# teensy_sid.net
KiCad netlist of a schematic drawn in EAGLE
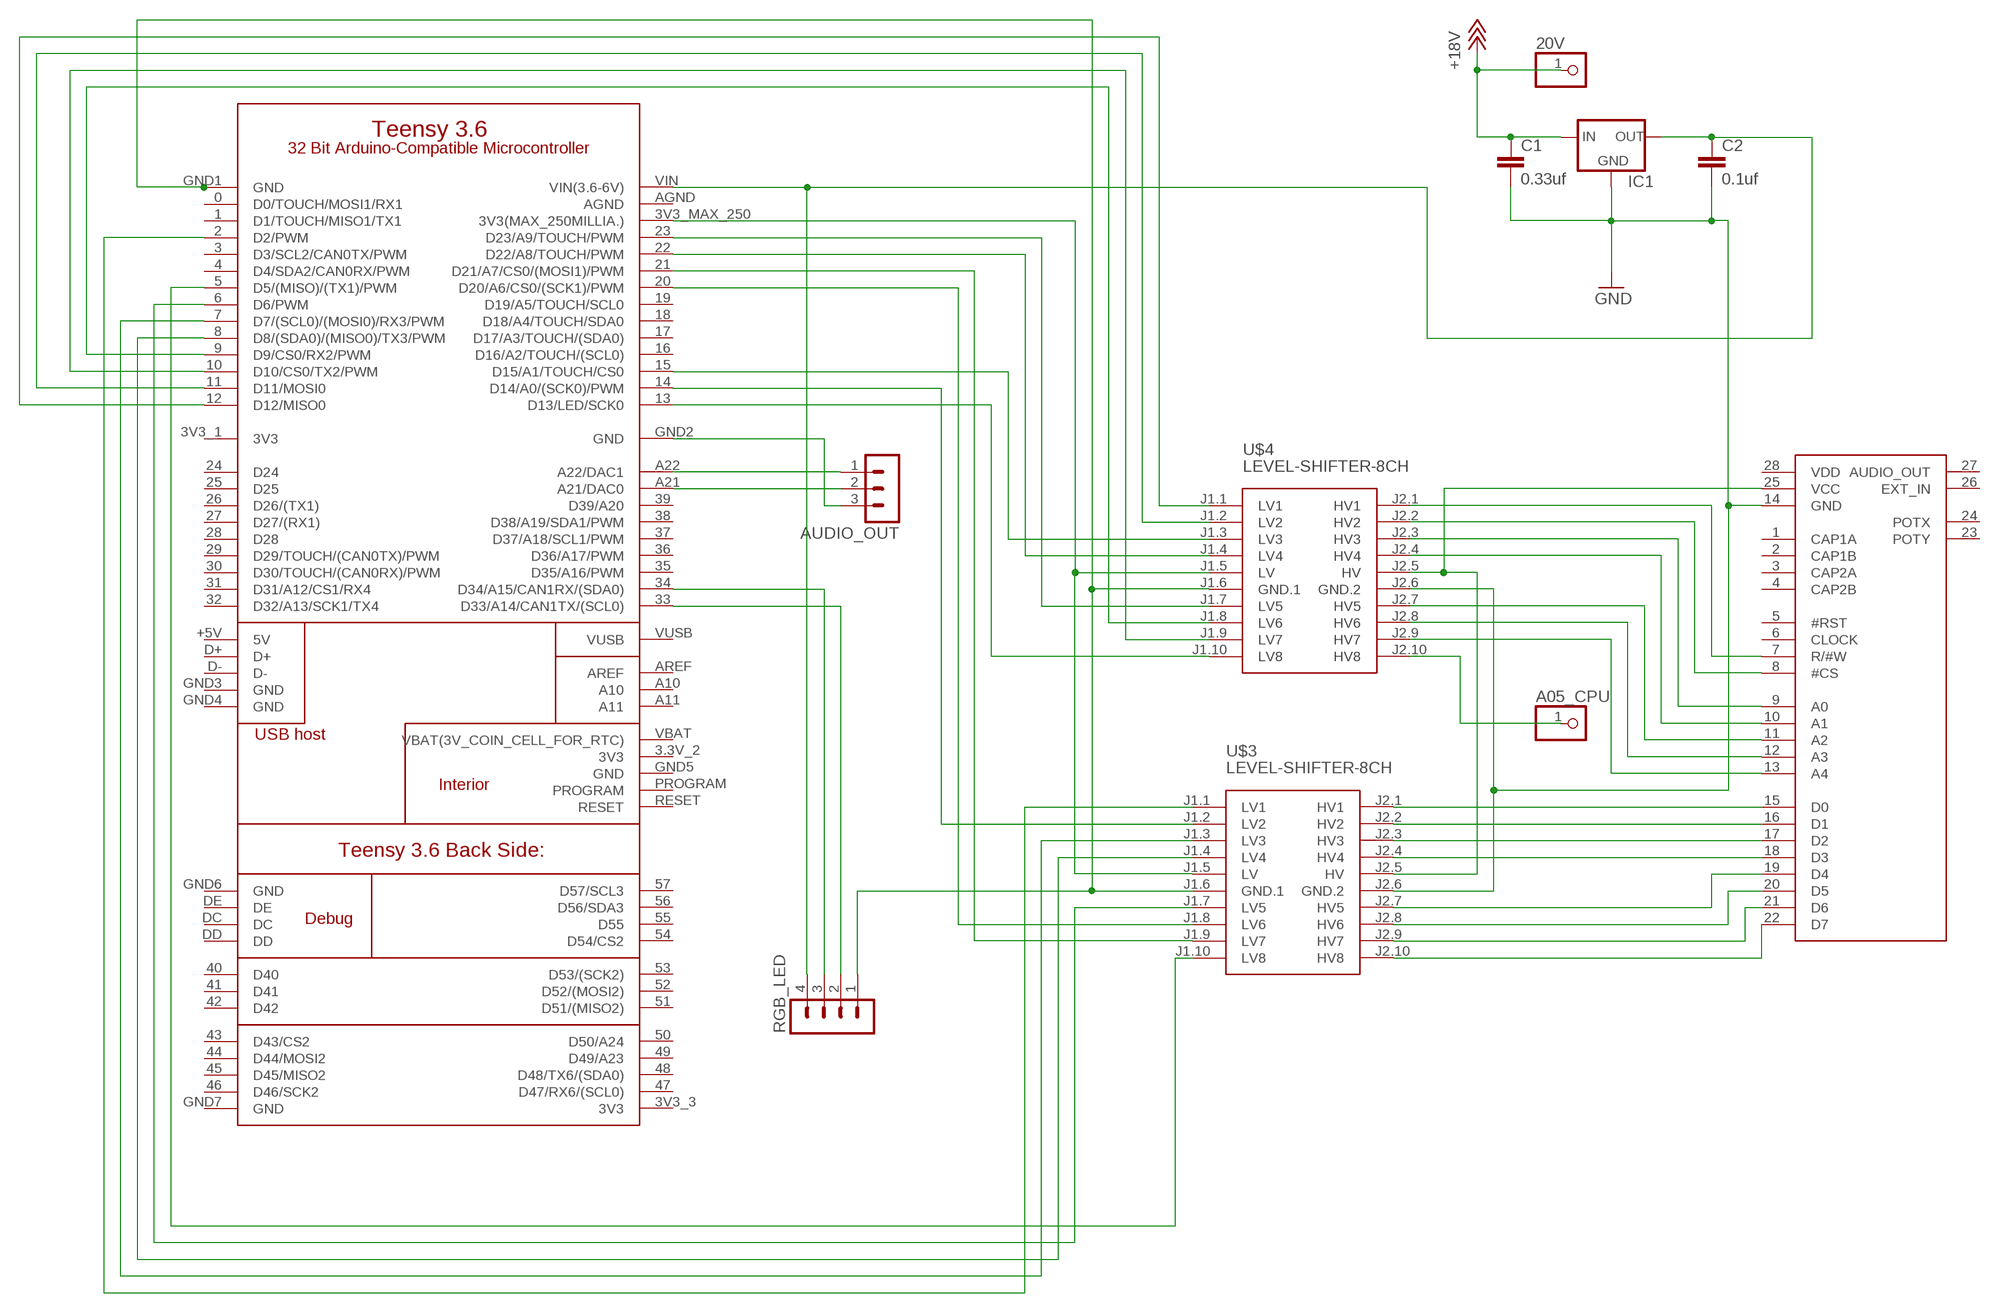
[diagram p0: schematic, sheet 1]

(export (version "E")
  (design (tool "Eeschema 10.0.6"))
  (components
    (comp (ref "20V")
      (value "PINHD-1X1")
      (footprint "eagle-import:1X01")
      (libsource (lib "eagle-import") (part "PINHD-1X1"))
    )
    (comp (ref "A05_CPU")
      (value "PINHD-1X1")
      (footprint "eagle-import:1X01")
      (libsource (lib "eagle-import") (part "PINHD-1X1"))
    )
    (comp (ref "AUDIO_OUT")
      (value "MA03-1")
      (footprint "eagle-import:MA03-1")
      (libsource (lib "eagle-import") (part "MA03-1"))
    )
    (comp (ref "C1")
      (value "0.33uf")
      (footprint "eagle-import:C025-024X044")
      (libsource (lib "eagle-import") (part "C-EU025-024X044"))
    )
    (comp (ref "C2")
      (value "0.1uf")
      (footprint "eagle-import:C025-024X044")
      (libsource (lib "eagle-import") (part "C-EU025-024X044"))
    )
    (comp (ref "IC1")
      (value "78XXL")
      (footprint "eagle-import:78XXL")
      (libsource (lib "eagle-import") (part "78XXL"))
    )
    (comp (ref "RGB_LED")
      (value "MA04-1")
      (footprint "eagle-import:MA04-1")
      (libsource (lib "eagle-import") (part "MA04-1"))
    )
    (comp (ref "U$1")
      (value "SID_6581")
      (footprint "eagle-import:DIL28-6")
      (libsource (lib "eagle-import") (part "SID_6581"))
    )
    (comp (ref "U$2")
      (value "TEENSY-3.6_FULL")
      (footprint "eagle-import:TEENSY-3.6_FULL")
      (libsource (lib "eagle-import") (part "TEENSY-3.6_FULL"))
    )
    (comp (ref "U$3")
      (value "LEVEL-SHIFTER-8CH")
      (footprint "eagle-import:LEVEL-SHIFTER-8CH")
      (libsource (lib "eagle-import") (part "LEVEL-SHIFTER-8CH"))
    )
    (comp (ref "U$4")
      (value "LEVEL-SHIFTER-8CH")
      (footprint "eagle-import:LEVEL-SHIFTER-8CH")
      (libsource (lib "eagle-import") (part "LEVEL-SHIFTER-8CH"))
    )
  )
  (nets
    (net (code "1") (name "+18V") (class "Default")
      (node (ref "20V") (pin "1") (pinfunction "1_1") (pintype "passive"))
      (node (ref "C1") (pin "1") (pinfunction "1_1") (pintype "passive"))
      (node (ref "IC1") (pin "IN") (pinfunction "IN_IN") (pintype "input"))
    )
    (net (code "2") (name "/3V3") (class "Default")
      (node (ref "U$2") (pin "3V3_1") (pinfunction "3V3_3V3_1") (pintype "power_in"))
    )
    (net (code "3") (name "/AGND") (class "Default")
      (node (ref "U$2") (pin "AGND") (pinfunction "AGND_AGND") (pintype "power_in"))
    )
    (net (code "4") (name "GND") (class "Default")
      (node (ref "C1") (pin "2") (pinfunction "2_2") (pintype "passive"))
      (node (ref "C2") (pin "2") (pinfunction "2_2") (pintype "passive"))
      (node (ref "IC1") (pin "GND") (pinfunction "GND_GND") (pintype "input"))
      (node (ref "U$1") (pin "14") (pinfunction "GND_14") (pintype "bidirectional"))
      (node (ref "U$3") (pin "J2.6") (pinfunction "GND.2_J2.6") (pintype "power_in"))
      (node (ref "U$4") (pin "J2.6") (pinfunction "GND.2_J2.6") (pintype "power_in"))
    )
    (net (code "5") (name "Net-(AUDIO_OUT-Pad3)") (class "Default")
      (node (ref "AUDIO_OUT") (pin "3") (pinfunction "3_3") (pintype "passive"))
      (node (ref "U$2") (pin "GND2") (pinfunction "GND_GND2") (pintype "power_in"))
    )
    (net (code "6") (name "Net-(U$1-#CS)") (class "Default")
      (node (ref "U$1") (pin "8") (pinfunction "#CS_8") (pintype "bidirectional"))
      (node (ref "U$4") (pin "J2.2") (pinfunction "HV2_J2.2") (pintype "bidirectional"))
    )
    (net (code "7") (name "Net-(U$1-A0)") (class "Default")
      (node (ref "U$1") (pin "9") (pinfunction "A0_9") (pintype "bidirectional"))
      (node (ref "U$4") (pin "J2.3") (pinfunction "HV3_J2.3") (pintype "bidirectional"))
    )
    (net (code "8") (name "Net-(U$1-A1)") (class "Default")
      (node (ref "U$1") (pin "10") (pinfunction "A1_10") (pintype "bidirectional"))
      (node (ref "U$4") (pin "J2.4") (pinfunction "HV4_J2.4") (pintype "bidirectional"))
    )
    (net (code "9") (name "Net-(U$1-A2)") (class "Default")
      (node (ref "U$1") (pin "11") (pinfunction "A2_11") (pintype "bidirectional"))
      (node (ref "U$4") (pin "J2.7") (pinfunction "HV5_J2.7") (pintype "bidirectional"))
    )
    (net (code "10") (name "Net-(U$1-A3)") (class "Default")
      (node (ref "U$1") (pin "12") (pinfunction "A3_12") (pintype "bidirectional"))
      (node (ref "U$4") (pin "J2.8") (pinfunction "HV6_J2.8") (pintype "bidirectional"))
    )
    (net (code "11") (name "Net-(U$1-A4)") (class "Default")
      (node (ref "U$1") (pin "13") (pinfunction "A4_13") (pintype "bidirectional"))
      (node (ref "U$4") (pin "J2.9") (pinfunction "HV7_J2.9") (pintype "bidirectional"))
    )
    (net (code "12") (name "Net-(U$1-D0)") (class "Default")
      (node (ref "U$1") (pin "15") (pinfunction "D0_15") (pintype "bidirectional"))
      (node (ref "U$3") (pin "J2.1") (pinfunction "HV1_J2.1") (pintype "bidirectional"))
    )
    (net (code "13") (name "Net-(U$1-D1)") (class "Default")
      (node (ref "U$1") (pin "16") (pinfunction "D1_16") (pintype "bidirectional"))
      (node (ref "U$3") (pin "J2.2") (pinfunction "HV2_J2.2") (pintype "bidirectional"))
    )
    (net (code "14") (name "Net-(U$1-D2)") (class "Default")
      (node (ref "U$1") (pin "17") (pinfunction "D2_17") (pintype "bidirectional"))
      (node (ref "U$3") (pin "J2.3") (pinfunction "HV3_J2.3") (pintype "bidirectional"))
    )
    (net (code "15") (name "Net-(U$1-D3)") (class "Default")
      (node (ref "U$1") (pin "18") (pinfunction "D3_18") (pintype "bidirectional"))
      (node (ref "U$3") (pin "J2.4") (pinfunction "HV4_J2.4") (pintype "bidirectional"))
    )
    (net (code "16") (name "Net-(U$1-D4)") (class "Default")
      (node (ref "U$1") (pin "19") (pinfunction "D4_19") (pintype "bidirectional"))
      (node (ref "U$3") (pin "J2.7") (pinfunction "HV5_J2.7") (pintype "bidirectional"))
    )
    (net (code "17") (name "Net-(U$1-D5)") (class "Default")
      (node (ref "U$1") (pin "20") (pinfunction "D5_20") (pintype "bidirectional"))
      (node (ref "U$3") (pin "J2.8") (pinfunction "HV6_J2.8") (pintype "bidirectional"))
    )
    (net (code "18") (name "Net-(U$1-D6)") (class "Default")
      (node (ref "U$1") (pin "21") (pinfunction "D6_21") (pintype "bidirectional"))
      (node (ref "U$3") (pin "J2.9") (pinfunction "HV7_J2.9") (pintype "bidirectional"))
    )
    (net (code "19") (name "Net-(U$1-D7)") (class "Default")
      (node (ref "U$1") (pin "22") (pinfunction "D7_22") (pintype "bidirectional"))
      (node (ref "U$3") (pin "J2.10") (pinfunction "HV8_J2.10") (pintype "bidirectional"))
    )
    (net (code "20") (name "Net-(U$1-R{slash}#W)") (class "Default")
      (node (ref "U$1") (pin "7") (pinfunction "R/#W_7") (pintype "bidirectional"))
      (node (ref "U$4") (pin "J2.1") (pinfunction "HV1_J2.1") (pintype "bidirectional"))
    )
    (net (code "21") (name "Net-(U$1-VCC)") (class "Default")
      (node (ref "U$1") (pin "25") (pinfunction "VCC_25") (pintype "bidirectional"))
      (node (ref "U$3") (pin "J2.5") (pinfunction "HV_J2.5") (pintype "power_in"))
      (node (ref "U$4") (pin "J2.5") (pinfunction "HV_J2.5") (pintype "power_in"))
    )
    (net (code "22") (name "Net-(U$2-3V3(MAX_250MILLIA.))") (class "Default")
      (node (ref "U$2") (pin "3V3_MAX_250") (pinfunction "3V3(MAX_250MILLIA.)_3V3_MAX_250") (pintype "bidirectional"))
      (node (ref "U$3") (pin "J1.5") (pinfunction "LV_J1.5") (pintype "power_in"))
      (node (ref "U$4") (pin "J1.5") (pinfunction "LV_J1.5") (pintype "power_in"))
    )
    (net (code "23") (name "Net-(U$2-A21{slash}DAC0)") (class "Default")
      (node (ref "AUDIO_OUT") (pin "2") (pinfunction "2_2") (pintype "passive"))
      (node (ref "U$2") (pin "A21") (pinfunction "A21/DAC0_A21") (pintype "bidirectional"))
    )
    (net (code "24") (name "Net-(U$2-A22{slash}DAC1)") (class "Default")
      (node (ref "AUDIO_OUT") (pin "1") (pinfunction "1_1") (pintype "passive"))
      (node (ref "U$2") (pin "A22") (pinfunction "A22/DAC1_A22") (pintype "bidirectional"))
    )
    (net (code "25") (name "Net-(U$2-D2{slash}PWM)") (class "Default")
      (node (ref "U$2") (pin "2") (pinfunction "D2/PWM_2") (pintype "bidirectional"))
      (node (ref "U$3") (pin "J1.1") (pinfunction "LV1_J1.1") (pintype "bidirectional"))
    )
    (net (code "26") (name "Net-(U$2-D5{slash}(MISO){slash}(TX1){slash}PWM)") (class "Default")
      (node (ref "U$2") (pin "5") (pinfunction "D5/(MISO)/(TX1)/PWM_5") (pintype "bidirectional"))
      (node (ref "U$3") (pin "J1.10") (pinfunction "LV8_J1.10") (pintype "bidirectional"))
    )
    (net (code "27") (name "Net-(U$2-D6{slash}PWM)") (class "Default")
      (node (ref "U$2") (pin "6") (pinfunction "D6/PWM_6") (pintype "bidirectional"))
      (node (ref "U$3") (pin "J1.7") (pinfunction "LV5_J1.7") (pintype "bidirectional"))
    )
    (net (code "28") (name "Net-(U$2-D7{slash}(SCL0){slash}(MOSI0){slash}RX3{slash}PWM)") (class "Default")
      (node (ref "U$2") (pin "7") (pinfunction "D7/(SCL0)/(MOSI0)/RX3/PWM_7") (pintype "bidirectional"))
      (node (ref "U$3") (pin "J1.3") (pinfunction "LV3_J1.3") (pintype "bidirectional"))
    )
    (net (code "29") (name "Net-(U$2-D8{slash}(SDA0){slash}(MISO0){slash}TX3{slash}PWM)") (class "Default")
      (node (ref "U$2") (pin "8") (pinfunction "D8/(SDA0)/(MISO0)/TX3/PWM_8") (pintype "bidirectional"))
      (node (ref "U$3") (pin "J1.4") (pinfunction "LV4_J1.4") (pintype "bidirectional"))
    )
    (net (code "30") (name "Net-(U$2-D9{slash}CS0{slash}RX2{slash}PWM)") (class "Default")
      (node (ref "U$2") (pin "9") (pinfunction "D9/CS0/RX2/PWM_9") (pintype "bidirectional"))
      (node (ref "U$4") (pin "J1.8") (pinfunction "LV6_J1.8") (pintype "bidirectional"))
    )
    (net (code "31") (name "Net-(U$2-D10{slash}CS0{slash}TX2{slash}PWM)") (class "Default")
      (node (ref "U$2") (pin "10") (pinfunction "D10/CS0/TX2/PWM_10") (pintype "bidirectional"))
      (node (ref "U$4") (pin "J1.9") (pinfunction "LV7_J1.9") (pintype "bidirectional"))
    )
    (net (code "32") (name "Net-(U$2-D11{slash}MOSI0)") (class "Default")
      (node (ref "U$2") (pin "11") (pinfunction "D11/MOSI0_11") (pintype "bidirectional"))
      (node (ref "U$4") (pin "J1.2") (pinfunction "LV2_J1.2") (pintype "bidirectional"))
    )
    (net (code "33") (name "Net-(U$2-D12{slash}MISO0)") (class "Default")
      (node (ref "U$2") (pin "12") (pinfunction "D12/MISO0_12") (pintype "bidirectional"))
      (node (ref "U$4") (pin "J1.1") (pinfunction "LV1_J1.1") (pintype "bidirectional"))
    )
    (net (code "34") (name "Net-(U$2-D13{slash}LED{slash}SCK0)") (class "Default")
      (node (ref "U$2") (pin "13") (pinfunction "D13/LED/SCK0_13") (pintype "bidirectional"))
      (node (ref "U$4") (pin "J1.10") (pinfunction "LV8_J1.10") (pintype "bidirectional"))
    )
    (net (code "35") (name "Net-(U$2-D14{slash}A0{slash}(SCK0){slash}PWM)") (class "Default")
      (node (ref "U$2") (pin "14") (pinfunction "D14/A0/(SCK0)/PWM_14") (pintype "bidirectional"))
      (node (ref "U$3") (pin "J1.2") (pinfunction "LV2_J1.2") (pintype "bidirectional"))
    )
    (net (code "36") (name "Net-(U$2-D15{slash}A1{slash}TOUCH{slash}CS0)") (class "Default")
      (node (ref "U$2") (pin "15") (pinfunction "D15/A1/TOUCH/CS0_15") (pintype "bidirectional"))
      (node (ref "U$4") (pin "J1.3") (pinfunction "LV3_J1.3") (pintype "bidirectional"))
    )
    (net (code "37") (name "Net-(U$2-D20{slash}A6{slash}CS0{slash}(SCK1){slash}PWM)") (class "Default")
      (node (ref "U$2") (pin "20") (pinfunction "D20/A6/CS0/(SCK1)/PWM_20") (pintype "bidirectional"))
      (node (ref "U$3") (pin "J1.8") (pinfunction "LV6_J1.8") (pintype "bidirectional"))
    )
    (net (code "38") (name "Net-(U$2-D21{slash}A7{slash}CS0{slash}(MOSI1){slash}PWM)") (class "Default")
      (node (ref "U$2") (pin "21") (pinfunction "D21/A7/CS0/(MOSI1)/PWM_21") (pintype "bidirectional"))
      (node (ref "U$3") (pin "J1.9") (pinfunction "LV7_J1.9") (pintype "bidirectional"))
    )
    (net (code "39") (name "Net-(U$2-D22{slash}A8{slash}TOUCH{slash}PWM)") (class "Default")
      (node (ref "U$2") (pin "22") (pinfunction "D22/A8/TOUCH/PWM_22") (pintype "bidirectional"))
      (node (ref "U$4") (pin "J1.4") (pinfunction "LV4_J1.4") (pintype "bidirectional"))
    )
    (net (code "40") (name "Net-(U$2-D23{slash}A9{slash}TOUCH{slash}PWM)") (class "Default")
      (node (ref "U$2") (pin "23") (pinfunction "D23/A9/TOUCH/PWM_23") (pintype "bidirectional"))
      (node (ref "U$4") (pin "J1.7") (pinfunction "LV5_J1.7") (pintype "bidirectional"))
    )
    (net (code "41") (name "Net-(U$2-D33{slash}A14{slash}CAN1TX{slash}(SCL0))") (class "Default")
      (node (ref "RGB_LED") (pin "2") (pinfunction "2_2") (pintype "passive"))
      (node (ref "U$2") (pin "33") (pinfunction "D33/A14/CAN1TX/(SCL0)_33") (pintype "bidirectional"))
    )
    (net (code "42") (name "Net-(U$2-D34{slash}A15{slash}CAN1RX{slash}(SDA0))") (class "Default")
      (node (ref "RGB_LED") (pin "3") (pinfunction "3_3") (pintype "passive"))
      (node (ref "U$2") (pin "34") (pinfunction "D34/A15/CAN1RX/(SDA0)_34") (pintype "bidirectional"))
    )
    (net (code "43") (name "Net-(U$2-VIN(3.6-6V))") (class "Default")
      (node (ref "C2") (pin "1") (pinfunction "1_1") (pintype "passive"))
      (node (ref "IC1") (pin "OUT") (pinfunction "OUT_OUT") (pintype "passive"))
      (node (ref "RGB_LED") (pin "4") (pinfunction "4_4") (pintype "passive"))
      (node (ref "U$2") (pin "VIN") (pinfunction "VIN(3.6-6V)_VIN") (pintype "power_in"))
    )
    (net (code "44") (name "Net-(U$3-GND.1)") (class "Default")
      (node (ref "RGB_LED") (pin "1") (pinfunction "1_1") (pintype "passive"))
      (node (ref "U$2") (pin "GND1") (pinfunction "GND_GND1") (pintype "power_in"))
      (node (ref "U$3") (pin "J1.6") (pinfunction "GND.1_J1.6") (pintype "power_in"))
      (node (ref "U$4") (pin "J1.6") (pinfunction "GND.1_J1.6") (pintype "power_in"))
    )
    (net (code "45") (name "Net-(U$4-HV8)") (class "Default")
      (node (ref "A05_CPU") (pin "1") (pinfunction "1_1") (pintype "passive"))
      (node (ref "U$4") (pin "J2.10") (pinfunction "HV8_J2.10") (pintype "bidirectional"))
    )
    (net (code "46") (name "unconnected-(U$1-#RST-Pad5)") (class "Default")
      (node (ref "U$1") (pin "5") (pinfunction "#RST_5") (pintype "bidirectional"))
    )
    (net (code "47") (name "unconnected-(U$1-AUDIO_OUT-Pad27)") (class "Default")
      (node (ref "U$1") (pin "27") (pinfunction "AUDIO_OUT_27") (pintype "bidirectional"))
    )
    (net (code "48") (name "unconnected-(U$1-CAP1A-Pad1)") (class "Default")
      (node (ref "U$1") (pin "1") (pinfunction "CAP1A_1") (pintype "bidirectional"))
    )
    (net (code "49") (name "unconnected-(U$1-CAP1B-Pad2)") (class "Default")
      (node (ref "U$1") (pin "2") (pinfunction "CAP1B_2") (pintype "bidirectional"))
    )
    (net (code "50") (name "unconnected-(U$1-CAP2A-Pad3)") (class "Default")
      (node (ref "U$1") (pin "3") (pinfunction "CAP2A_3") (pintype "bidirectional"))
    )
    (net (code "51") (name "unconnected-(U$1-CAP2B-Pad4)") (class "Default")
      (node (ref "U$1") (pin "4") (pinfunction "CAP2B_4") (pintype "bidirectional"))
    )
    (net (code "52") (name "unconnected-(U$1-CLOCK-Pad6)") (class "Default")
      (node (ref "U$1") (pin "6") (pinfunction "CLOCK_6") (pintype "bidirectional"))
    )
    (net (code "53") (name "unconnected-(U$1-EXT_IN-Pad26)") (class "Default")
      (node (ref "U$1") (pin "26") (pinfunction "EXT_IN_26") (pintype "bidirectional"))
    )
    (net (code "54") (name "unconnected-(U$1-POTX-Pad24)") (class "Default")
      (node (ref "U$1") (pin "24") (pinfunction "POTX_24") (pintype "bidirectional"))
    )
    (net (code "55") (name "unconnected-(U$1-POTY-Pad23)") (class "Default")
      (node (ref "U$1") (pin "23") (pinfunction "POTY_23") (pintype "bidirectional"))
    )
    (net (code "56") (name "unconnected-(U$1-VDD-Pad28)") (class "Default")
      (node (ref "U$1") (pin "28") (pinfunction "VDD_28") (pintype "bidirectional"))
    )
    (net (code "57") (name "unconnected-(U$2-3V3-Pad3.3V_2)") (class "Default")
      (node (ref "U$2") (pin "3.3V_2") (pinfunction "3V3_3.3V_2") (pintype "bidirectional"))
    )
    (net (code "58") (name "unconnected-(U$2-3V3-Pad3V3_3)") (class "Default")
      (node (ref "U$2") (pin "3V3_3") (pinfunction "3V3_3V3_3") (pintype "bidirectional"))
    )
    (net (code "59") (name "unconnected-(U$2-5V-Pad+5V)") (class "Default")
      (node (ref "U$2") (pin "+5V") (pinfunction "5V_+5V") (pintype "bidirectional"))
    )
    (net (code "60") (name "unconnected-(U$2-D0{slash}TOUCH{slash}MOSI1{slash}RX1-Pad0)") (class "Default")
      (node (ref "U$2") (pin "0") (pinfunction "D0/TOUCH/MOSI1/RX1_0") (pintype "bidirectional"))
    )
    (net (code "61") (name "unconnected-(U$2-D1{slash}TOUCH{slash}MISO1{slash}TX1-Pad1)") (class "Default")
      (node (ref "U$2") (pin "1") (pinfunction "D1/TOUCH/MISO1/TX1_1") (pintype "bidirectional"))
    )
    (net (code "62") (name "unconnected-(U$2-D3{slash}SCL2{slash}CAN0TX{slash}PWM-Pad3)") (class "Default")
      (node (ref "U$2") (pin "3") (pinfunction "D3/SCL2/CAN0TX/PWM_3") (pintype "bidirectional"))
    )
    (net (code "63") (name "unconnected-(U$2-D4{slash}SDA2{slash}CAN0RX{slash}PWM-Pad4)") (class "Default")
      (node (ref "U$2") (pin "4") (pinfunction "D4/SDA2/CAN0RX/PWM_4") (pintype "bidirectional"))
    )
    (net (code "64") (name "unconnected-(U$2-D16{slash}A2{slash}TOUCH{slash}(SCL0)-Pad16)") (class "Default")
      (node (ref "U$2") (pin "16") (pinfunction "D16/A2/TOUCH/(SCL0)_16") (pintype "bidirectional"))
    )
    (net (code "65") (name "unconnected-(U$2-D17{slash}A3{slash}TOUCH{slash}(SDA0)-Pad17)") (class "Default")
      (node (ref "U$2") (pin "17") (pinfunction "D17/A3/TOUCH/(SDA0)_17") (pintype "bidirectional"))
    )
    (net (code "66") (name "unconnected-(U$2-D18{slash}A4{slash}TOUCH{slash}SDA0-Pad18)") (class "Default")
      (node (ref "U$2") (pin "18") (pinfunction "D18/A4/TOUCH/SDA0_18") (pintype "bidirectional"))
    )
    (net (code "67") (name "unconnected-(U$2-D19{slash}A5{slash}TOUCH{slash}SCL0-Pad19)") (class "Default")
      (node (ref "U$2") (pin "19") (pinfunction "D19/A5/TOUCH/SCL0_19") (pintype "bidirectional"))
    )
    (net (code "68") (name "unconnected-(U$2-D24-Pad24)") (class "Default")
      (node (ref "U$2") (pin "24") (pinfunction "D24_24") (pintype "bidirectional"))
    )
    (net (code "69") (name "unconnected-(U$2-D25-Pad25)") (class "Default")
      (node (ref "U$2") (pin "25") (pinfunction "D25_25") (pintype "bidirectional"))
    )
    (net (code "70") (name "unconnected-(U$2-D26{slash}(TX1)-Pad26)") (class "Default")
      (node (ref "U$2") (pin "26") (pinfunction "D26/(TX1)_26") (pintype "bidirectional"))
    )
    (net (code "71") (name "unconnected-(U$2-D27{slash}(RX1)-Pad27)") (class "Default")
      (node (ref "U$2") (pin "27") (pinfunction "D27/(RX1)_27") (pintype "bidirectional"))
    )
    (net (code "72") (name "unconnected-(U$2-D28-Pad28)") (class "Default")
      (node (ref "U$2") (pin "28") (pinfunction "D28_28") (pintype "bidirectional"))
    )
    (net (code "73") (name "unconnected-(U$2-D29{slash}TOUCH{slash}(CAN0TX){slash}PWM-Pad29)") (class "Default")
      (node (ref "U$2") (pin "29") (pinfunction "D29/TOUCH/(CAN0TX)/PWM_29") (pintype "bidirectional"))
    )
    (net (code "74") (name "unconnected-(U$2-D30{slash}TOUCH{slash}(CAN0RX){slash}PWM-Pad30)") (class "Default")
      (node (ref "U$2") (pin "30") (pinfunction "D30/TOUCH/(CAN0RX)/PWM_30") (pintype "bidirectional"))
    )
    (net (code "75") (name "unconnected-(U$2-D31{slash}A12{slash}CS1{slash}RX4-Pad31)") (class "Default")
      (node (ref "U$2") (pin "31") (pinfunction "D31/A12/CS1/RX4_31") (pintype "bidirectional"))
    )
    (net (code "76") (name "unconnected-(U$2-D32{slash}A13{slash}SCK1{slash}TX4-Pad32)") (class "Default")
      (node (ref "U$2") (pin "32") (pinfunction "D32/A13/SCK1/TX4_32") (pintype "bidirectional"))
    )
    (net (code "77") (name "unconnected-(U$2-D35{slash}A16{slash}PWM-Pad35)") (class "Default")
      (node (ref "U$2") (pin "35") (pinfunction "D35/A16/PWM_35") (pintype "bidirectional"))
    )
    (net (code "78") (name "unconnected-(U$2-D36{slash}A17{slash}PWM-Pad36)") (class "Default")
      (node (ref "U$2") (pin "36") (pinfunction "D36/A17/PWM_36") (pintype "bidirectional"))
    )
    (net (code "79") (name "unconnected-(U$2-D37{slash}A18{slash}SCL1{slash}PWM-Pad37)") (class "Default")
      (node (ref "U$2") (pin "37") (pinfunction "D37/A18/SCL1/PWM_37") (pintype "bidirectional"))
    )
    (net (code "80") (name "unconnected-(U$2-D38{slash}A19{slash}SDA1{slash}PWM-Pad38)") (class "Default")
      (node (ref "U$2") (pin "38") (pinfunction "D38/A19/SDA1/PWM_38") (pintype "bidirectional"))
    )
    (net (code "81") (name "unconnected-(U$2-D39{slash}A20-Pad39)") (class "Default")
      (node (ref "U$2") (pin "39") (pinfunction "D39/A20_39") (pintype "bidirectional"))
    )
    (net (code "82") (name "unconnected-(U$2-D40-Pad40)") (class "Default")
      (node (ref "U$2") (pin "40") (pinfunction "D40_40") (pintype "bidirectional"))
    )
    (net (code "83") (name "unconnected-(U$2-D41-Pad41)") (class "Default")
      (node (ref "U$2") (pin "41") (pinfunction "D41_41") (pintype "bidirectional"))
    )
    (net (code "84") (name "unconnected-(U$2-D42-Pad42)") (class "Default")
      (node (ref "U$2") (pin "42") (pinfunction "D42_42") (pintype "bidirectional"))
    )
    (net (code "85") (name "unconnected-(U$2-D43{slash}CS2-Pad43)") (class "Default")
      (node (ref "U$2") (pin "43") (pinfunction "D43/CS2_43") (pintype "bidirectional"))
    )
    (net (code "86") (name "unconnected-(U$2-D44{slash}MOSI2-Pad44)") (class "Default")
      (node (ref "U$2") (pin "44") (pinfunction "D44/MOSI2_44") (pintype "bidirectional"))
    )
    (net (code "87") (name "unconnected-(U$2-D45{slash}MISO2-Pad45)") (class "Default")
      (node (ref "U$2") (pin "45") (pinfunction "D45/MISO2_45") (pintype "bidirectional"))
    )
    (net (code "88") (name "unconnected-(U$2-D46{slash}SCK2-Pad46)") (class "Default")
      (node (ref "U$2") (pin "46") (pinfunction "D46/SCK2_46") (pintype "bidirectional"))
    )
    (net (code "89") (name "unconnected-(U$2-D47{slash}RX6{slash}(SCL0)-Pad47)") (class "Default")
      (node (ref "U$2") (pin "47") (pinfunction "D47/RX6/(SCL0)_47") (pintype "bidirectional"))
    )
    (net (code "90") (name "unconnected-(U$2-D48{slash}TX6{slash}(SDA0)-Pad48)") (class "Default")
      (node (ref "U$2") (pin "48") (pinfunction "D48/TX6/(SDA0)_48") (pintype "bidirectional"))
    )
    (net (code "91") (name "unconnected-(U$2-D49{slash}A23-Pad49)") (class "Default")
      (node (ref "U$2") (pin "49") (pinfunction "D49/A23_49") (pintype "bidirectional"))
    )
    (net (code "92") (name "unconnected-(U$2-D50{slash}A24-Pad50)") (class "Default")
      (node (ref "U$2") (pin "50") (pinfunction "D50/A24_50") (pintype "bidirectional"))
    )
    (net (code "93") (name "unconnected-(U$2-D51{slash}(MISO2)-Pad51)") (class "Default")
      (node (ref "U$2") (pin "51") (pinfunction "D51/(MISO2)_51") (pintype "bidirectional"))
    )
    (net (code "94") (name "unconnected-(U$2-D52{slash}(MOSI2)-Pad52)") (class "Default")
      (node (ref "U$2") (pin "52") (pinfunction "D52/(MOSI2)_52") (pintype "bidirectional"))
    )
    (net (code "95") (name "unconnected-(U$2-D53{slash}(SCK2)-Pad53)") (class "Default")
      (node (ref "U$2") (pin "53") (pinfunction "D53/(SCK2)_53") (pintype "bidirectional"))
    )
    (net (code "96") (name "unconnected-(U$2-D54{slash}CS2-Pad54)") (class "Default")
      (node (ref "U$2") (pin "54") (pinfunction "D54/CS2_54") (pintype "bidirectional"))
    )
    (net (code "97") (name "unconnected-(U$2-D55-Pad55)") (class "Default")
      (node (ref "U$2") (pin "55") (pinfunction "D55_55") (pintype "bidirectional"))
    )
    (net (code "98") (name "unconnected-(U$2-D56{slash}SDA3-Pad56)") (class "Default")
      (node (ref "U$2") (pin "56") (pinfunction "D56/SDA3_56") (pintype "bidirectional"))
    )
    (net (code "99") (name "unconnected-(U$2-D57{slash}SCL3-Pad57)") (class "Default")
      (node (ref "U$2") (pin "57") (pinfunction "D57/SCL3_57") (pintype "bidirectional"))
    )
    (net (code "100") (name "unconnected-(U$2-GND-PadGND3)") (class "Default")
      (node (ref "U$2") (pin "GND3") (pinfunction "GND_GND3") (pintype "bidirectional"))
    )
    (net (code "101") (name "unconnected-(U$2-GND-PadGND4)") (class "Default")
      (node (ref "U$2") (pin "GND4") (pinfunction "GND_GND4") (pintype "bidirectional"))
    )
    (net (code "102") (name "unconnected-(U$2-GND-PadGND5)") (class "Default")
      (node (ref "U$2") (pin "GND5") (pinfunction "GND_GND5") (pintype "bidirectional"))
    )
    (net (code "103") (name "unconnected-(U$2-GND-PadGND6)") (class "Default")
      (node (ref "U$2") (pin "GND6") (pinfunction "GND_GND6") (pintype "bidirectional"))
    )
    (net (code "104") (name "unconnected-(U$2-GND-PadGND7)") (class "Default")
      (node (ref "U$2") (pin "GND7") (pinfunction "GND_GND7") (pintype "bidirectional"))
    )
    (net (code "105") (name "unconnected-(U$2-PadA10)") (class "Default")
      (node (ref "U$2") (pin "A10") (pinfunction "A10_A10") (pintype "bidirectional"))
    )
    (net (code "106") (name "unconnected-(U$2-PadA11)") (class "Default")
      (node (ref "U$2") (pin "A11") (pinfunction "A11_A11") (pintype "bidirectional"))
    )
    (net (code "107") (name "unconnected-(U$2-PadAREF)") (class "Default")
      (node (ref "U$2") (pin "AREF") (pinfunction "AREF_AREF") (pintype "bidirectional"))
    )
    (net (code "108") (name "unconnected-(U$2-PadD+)") (class "Default")
      (node (ref "U$2") (pin "D+") (pinfunction "D+_D+") (pintype "bidirectional"))
    )
    (net (code "109") (name "unconnected-(U$2-PadD-)") (class "Default")
      (node (ref "U$2") (pin "D-") (pinfunction "D-_D-") (pintype "bidirectional"))
    )
    (net (code "110") (name "unconnected-(U$2-PadDC)") (class "Default")
      (node (ref "U$2") (pin "DC") (pinfunction "DC_DC") (pintype "bidirectional"))
    )
    (net (code "111") (name "unconnected-(U$2-PadDD)") (class "Default")
      (node (ref "U$2") (pin "DD") (pinfunction "DD_DD") (pintype "bidirectional"))
    )
    (net (code "112") (name "unconnected-(U$2-PadDE)") (class "Default")
      (node (ref "U$2") (pin "DE") (pinfunction "DE_DE") (pintype "bidirectional"))
    )
    (net (code "113") (name "unconnected-(U$2-PadPROGRAM)") (class "Default")
      (node (ref "U$2") (pin "PROGRAM") (pinfunction "PROGRAM_PROGRAM") (pintype "bidirectional"))
    )
    (net (code "114") (name "unconnected-(U$2-PadRESET)") (class "Default")
      (node (ref "U$2") (pin "RESET") (pinfunction "RESET_RESET") (pintype "bidirectional"))
    )
    (net (code "115") (name "unconnected-(U$2-PadVUSB)") (class "Default")
      (node (ref "U$2") (pin "VUSB") (pinfunction "VUSB_VUSB") (pintype "bidirectional"))
    )
    (net (code "116") (name "unconnected-(U$2-VBAT(3V_COIN_CELL_FOR_RTC)-PadVBAT)") (class "Default")
      (node (ref "U$2") (pin "VBAT") (pinfunction "VBAT(3V_COIN_CELL_FOR_RTC)_VBAT") (pintype "bidirectional"))
    )
  )
)
